# Memory.net
KiCad netlist of a schematic drawn in Altium Designer
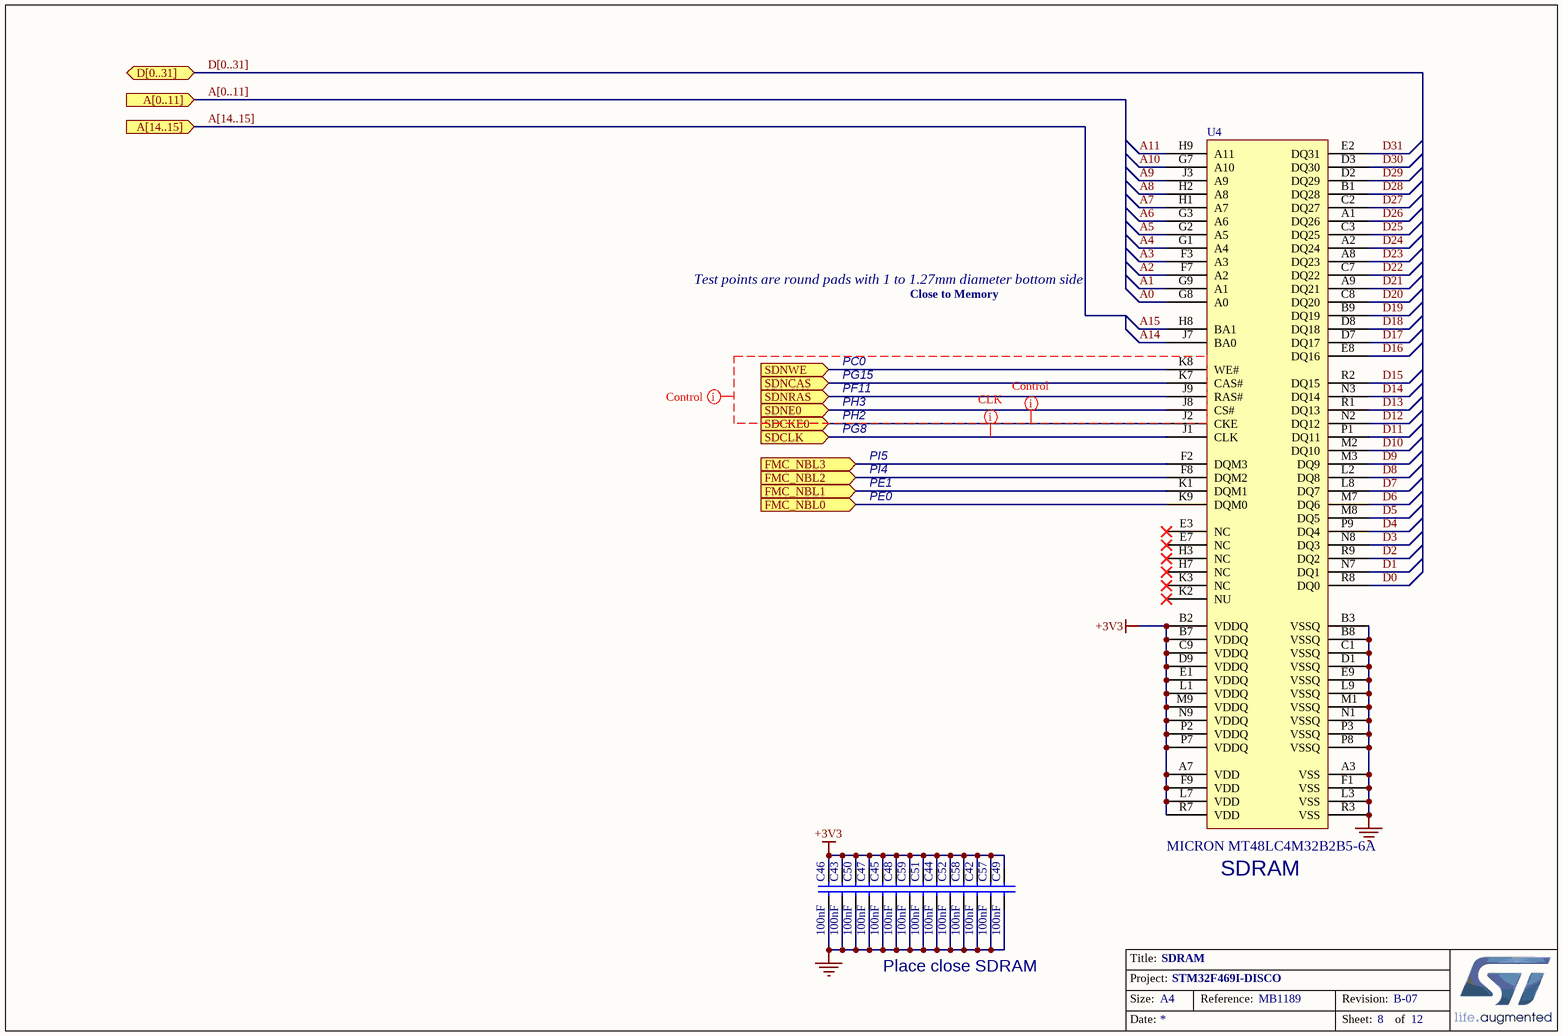
[diagram p0: Memory.SchDoc]

(export (version "E")
  (design (tool "Eeschema 10.0.6"))
  (components
    (comp (ref "C42")
      (value "100nF")
      (footprint "CAP - 0402")
      (description "Capacitor")
      (fields (field (name "PUBLISHER") "Altium Limited"))
      (libsource (lib "Miscellaneous Devices") (part "Cap"))
    )
    (comp (ref "C43")
      (value "100nF")
      (footprint "CAP - 0402")
      (description "Capacitor")
      (fields (field (name "PUBLISHER") "Altium Limited"))
      (libsource (lib "Miscellaneous Devices") (part "Cap"))
    )
    (comp (ref "C44")
      (value "100nF")
      (footprint "CAP - 0402")
      (description "Capacitor")
      (fields (field (name "PUBLISHER") "Altium Limited"))
      (libsource (lib "Miscellaneous Devices") (part "Cap"))
    )
    (comp (ref "C45")
      (value "100nF")
      (footprint "CAP - 0402")
      (description "Capacitor")
      (fields (field (name "PUBLISHER") "Altium Limited"))
      (libsource (lib "Miscellaneous Devices") (part "Cap"))
    )
    (comp (ref "C46")
      (value "100nF")
      (footprint "CAP - 0402")
      (description "Capacitor")
      (fields (field (name "PUBLISHER") "Altium Limited"))
      (libsource (lib "Miscellaneous Devices") (part "Cap"))
    )
    (comp (ref "C47")
      (value "100nF")
      (footprint "CAP - 0402")
      (description "Capacitor")
      (fields (field (name "PUBLISHER") "Altium Limited"))
      (libsource (lib "Miscellaneous Devices") (part "Cap"))
    )
    (comp (ref "C48")
      (value "100nF")
      (footprint "CAP - 0402")
      (description "Capacitor")
      (fields (field (name "PUBLISHER") "Altium Limited"))
      (libsource (lib "Miscellaneous Devices") (part "Cap"))
    )
    (comp (ref "C49")
      (value "100nF")
      (footprint "CAP - 0402")
      (description "Capacitor")
      (fields (field (name "PUBLISHER") "Altium Limited"))
      (libsource (lib "Miscellaneous Devices") (part "Cap"))
    )
    (comp (ref "C50")
      (value "100nF")
      (footprint "CAP - 0402")
      (description "Capacitor")
      (fields (field (name "PUBLISHER") "Altium Limited"))
      (libsource (lib "Miscellaneous Devices") (part "Cap"))
    )
    (comp (ref "C51")
      (value "100nF")
      (footprint "CAP - 0402")
      (description "Capacitor")
      (fields (field (name "PUBLISHER") "Altium Limited"))
      (libsource (lib "Miscellaneous Devices") (part "Cap"))
    )
    (comp (ref "C52")
      (value "100nF")
      (footprint "CAP - 0402")
      (description "Capacitor")
      (fields (field (name "PUBLISHER") "Altium Limited"))
      (libsource (lib "Miscellaneous Devices") (part "Cap"))
    )
    (comp (ref "C57")
      (value "100nF")
      (footprint "CAP - 0402")
      (description "Capacitor")
      (fields (field (name "PUBLISHER") "Altium Limited"))
      (libsource (lib "Miscellaneous Devices") (part "Cap"))
    )
    (comp (ref "C58")
      (value "100nF")
      (footprint "CAP - 0402")
      (description "Capacitor")
      (fields (field (name "PUBLISHER") "Altium Limited"))
      (libsource (lib "Miscellaneous Devices") (part "Cap"))
    )
    (comp (ref "C59")
      (value "100nF")
      (footprint "CAP - 0402")
      (description "Capacitor")
      (fields (field (name "PUBLISHER") "Altium Limited"))
      (libsource (lib "Miscellaneous Devices") (part "Cap"))
    )
    (comp (ref "U4")
      (value "MICRON MT48LC4M32B2B5-6A")
      (footprint "MICT-B5-90")
      (libsource (lib "mb1045") (part "MT48LC4M32B2B5"))
    )
  )
  (nets
    (net (code "1") (name "+3V3") (class "Default")
      (node (ref "C42") (pin "1") (pinfunction "1_1") (pintype "passive"))
      (node (ref "C43") (pin "1") (pinfunction "1_1") (pintype "passive"))
      (node (ref "C44") (pin "1") (pinfunction "1_1") (pintype "passive"))
      (node (ref "C45") (pin "1") (pinfunction "1_1") (pintype "passive"))
      (node (ref "C46") (pin "1") (pinfunction "1_1") (pintype "passive"))
      (node (ref "C47") (pin "1") (pinfunction "1_1") (pintype "passive"))
      (node (ref "C48") (pin "1") (pinfunction "1_1") (pintype "passive"))
      (node (ref "C49") (pin "1") (pinfunction "1_1") (pintype "passive"))
      (node (ref "C50") (pin "1") (pinfunction "1_1") (pintype "passive"))
      (node (ref "C51") (pin "1") (pinfunction "1_1") (pintype "passive"))
      (node (ref "C52") (pin "1") (pinfunction "1_1") (pintype "passive"))
      (node (ref "C57") (pin "1") (pinfunction "1_1") (pintype "passive"))
      (node (ref "C58") (pin "1") (pinfunction "1_1") (pintype "passive"))
      (node (ref "C59") (pin "1") (pinfunction "1_1") (pintype "passive"))
      (node (ref "U4") (pin "A7") (pinfunction "VDD_A7") (pintype "passive"))
      (node (ref "U4") (pin "B2") (pinfunction "VDDQ_B2") (pintype "passive"))
      (node (ref "U4") (pin "B7") (pinfunction "VDDQ_B7") (pintype "passive"))
      (node (ref "U4") (pin "C9") (pinfunction "VDDQ_C9") (pintype "passive"))
      (node (ref "U4") (pin "D9") (pinfunction "VDDQ_D9") (pintype "passive"))
      (node (ref "U4") (pin "E1") (pinfunction "VDDQ_E1") (pintype "passive"))
      (node (ref "U4") (pin "F9") (pinfunction "VDD_F9") (pintype "passive"))
      (node (ref "U4") (pin "L1") (pinfunction "VDDQ_L1") (pintype "passive"))
      (node (ref "U4") (pin "L7") (pinfunction "VDD_L7") (pintype "passive"))
      (node (ref "U4") (pin "M9") (pinfunction "VDDQ_M9") (pintype "passive"))
      (node (ref "U4") (pin "N9") (pinfunction "VDDQ_N9") (pintype "passive"))
      (node (ref "U4") (pin "P2") (pinfunction "VDDQ_P2") (pintype "passive"))
      (node (ref "U4") (pin "P7") (pinfunction "VDDQ_P7") (pintype "passive"))
      (node (ref "U4") (pin "R7") (pinfunction "VDD_R7") (pintype "passive"))
    )
    (net (code "2") (name "/A0") (class "Default")
      (node (ref "U4") (pin "G8") (pinfunction "A0_G8") (pintype "passive"))
    )
    (net (code "3") (name "/A1") (class "Default")
      (node (ref "U4") (pin "G9") (pinfunction "A1_G9") (pintype "passive"))
    )
    (net (code "4") (name "/A2") (class "Default")
      (node (ref "U4") (pin "F7") (pinfunction "A2_F7") (pintype "passive"))
    )
    (net (code "5") (name "/A3") (class "Default")
      (node (ref "U4") (pin "F3") (pinfunction "A3_F3") (pintype "passive"))
    )
    (net (code "6") (name "/A4") (class "Default")
      (node (ref "U4") (pin "G1") (pinfunction "A4_G1") (pintype "passive"))
    )
    (net (code "7") (name "/A5") (class "Default")
      (node (ref "U4") (pin "G2") (pinfunction "A5_G2") (pintype "passive"))
    )
    (net (code "8") (name "/A6") (class "Default")
      (node (ref "U4") (pin "G3") (pinfunction "A6_G3") (pintype "passive"))
    )
    (net (code "9") (name "/A7") (class "Default")
      (node (ref "U4") (pin "H1") (pinfunction "A7_H1") (pintype "passive"))
    )
    (net (code "10") (name "/A8") (class "Default")
      (node (ref "U4") (pin "H2") (pinfunction "A8_H2") (pintype "passive"))
    )
    (net (code "11") (name "/A9") (class "Default")
      (node (ref "U4") (pin "J3") (pinfunction "A9_J3") (pintype "passive"))
    )
    (net (code "12") (name "/A10") (class "Default")
      (node (ref "U4") (pin "G7") (pinfunction "A10_G7") (pintype "passive"))
    )
    (net (code "13") (name "/A11") (class "Default")
      (node (ref "U4") (pin "H9") (pinfunction "A11_H9") (pintype "passive"))
    )
    (net (code "14") (name "/A14") (class "Default")
      (node (ref "U4") (pin "J7") (pinfunction "BA0_J7") (pintype "passive"))
    )
    (net (code "15") (name "/A15") (class "Default")
      (node (ref "U4") (pin "H8") (pinfunction "BA1_H8") (pintype "passive"))
    )
    (net (code "18") (name "/D0") (class "Default")
      (node (ref "U4") (pin "R8") (pinfunction "DQ0_R8") (pintype "passive"))
    )
    (net (code "19") (name "/D1") (class "Default")
      (node (ref "U4") (pin "N7") (pinfunction "DQ1_N7") (pintype "passive"))
    )
    (net (code "20") (name "/D2") (class "Default")
      (node (ref "U4") (pin "R9") (pinfunction "DQ2_R9") (pintype "passive"))
    )
    (net (code "21") (name "/D3") (class "Default")
      (node (ref "U4") (pin "N8") (pinfunction "DQ3_N8") (pintype "passive"))
    )
    (net (code "22") (name "/D4") (class "Default")
      (node (ref "U4") (pin "P9") (pinfunction "DQ4_P9") (pintype "passive"))
    )
    (net (code "23") (name "/D5") (class "Default")
      (node (ref "U4") (pin "M8") (pinfunction "DQ5_M8") (pintype "passive"))
    )
    (net (code "24") (name "/D6") (class "Default")
      (node (ref "U4") (pin "M7") (pinfunction "DQ6_M7") (pintype "passive"))
    )
    (net (code "25") (name "/D7") (class "Default")
      (node (ref "U4") (pin "L8") (pinfunction "DQ7_L8") (pintype "passive"))
    )
    (net (code "26") (name "/D8") (class "Default")
      (node (ref "U4") (pin "L2") (pinfunction "DQ8_L2") (pintype "passive"))
    )
    (net (code "27") (name "/D9") (class "Default")
      (node (ref "U4") (pin "M3") (pinfunction "DQ9_M3") (pintype "passive"))
    )
    (net (code "28") (name "/D10") (class "Default")
      (node (ref "U4") (pin "M2") (pinfunction "DQ10_M2") (pintype "passive"))
    )
    (net (code "29") (name "/D11") (class "Default")
      (node (ref "U4") (pin "P1") (pinfunction "DQ11_P1") (pintype "passive"))
    )
    (net (code "30") (name "/D12") (class "Default")
      (node (ref "U4") (pin "N2") (pinfunction "DQ12_N2") (pintype "passive"))
    )
    (net (code "31") (name "/D13") (class "Default")
      (node (ref "U4") (pin "R1") (pinfunction "DQ13_R1") (pintype "passive"))
    )
    (net (code "32") (name "/D14") (class "Default")
      (node (ref "U4") (pin "N3") (pinfunction "DQ14_N3") (pintype "passive"))
    )
    (net (code "33") (name "/D15") (class "Default")
      (node (ref "U4") (pin "R2") (pinfunction "DQ15_R2") (pintype "passive"))
    )
    (net (code "34") (name "/D16") (class "Default")
      (node (ref "U4") (pin "E8") (pinfunction "DQ16_E8") (pintype "passive"))
    )
    (net (code "35") (name "/D17") (class "Default")
      (node (ref "U4") (pin "D7") (pinfunction "DQ17_D7") (pintype "passive"))
    )
    (net (code "36") (name "/D18") (class "Default")
      (node (ref "U4") (pin "D8") (pinfunction "DQ18_D8") (pintype "passive"))
    )
    (net (code "37") (name "/D19") (class "Default")
      (node (ref "U4") (pin "B9") (pinfunction "DQ19_B9") (pintype "passive"))
    )
    (net (code "38") (name "/D20") (class "Default")
      (node (ref "U4") (pin "C8") (pinfunction "DQ20_C8") (pintype "passive"))
    )
    (net (code "39") (name "/D21") (class "Default")
      (node (ref "U4") (pin "A9") (pinfunction "DQ21_A9") (pintype "passive"))
    )
    (net (code "40") (name "/D22") (class "Default")
      (node (ref "U4") (pin "C7") (pinfunction "DQ22_C7") (pintype "passive"))
    )
    (net (code "41") (name "/D23") (class "Default")
      (node (ref "U4") (pin "A8") (pinfunction "DQ23_A8") (pintype "passive"))
    )
    (net (code "42") (name "/D24") (class "Default")
      (node (ref "U4") (pin "A2") (pinfunction "DQ24_A2") (pintype "passive"))
    )
    (net (code "43") (name "/D25") (class "Default")
      (node (ref "U4") (pin "C3") (pinfunction "DQ25_C3") (pintype "passive"))
    )
    (net (code "44") (name "/D26") (class "Default")
      (node (ref "U4") (pin "A1") (pinfunction "DQ26_A1") (pintype "passive"))
    )
    (net (code "45") (name "/D27") (class "Default")
      (node (ref "U4") (pin "C2") (pinfunction "DQ27_C2") (pintype "passive"))
    )
    (net (code "46") (name "/D28") (class "Default")
      (node (ref "U4") (pin "B1") (pinfunction "DQ28_B1") (pintype "passive"))
    )
    (net (code "47") (name "/D29") (class "Default")
      (node (ref "U4") (pin "D2") (pinfunction "DQ29_D2") (pintype "passive"))
    )
    (net (code "48") (name "/D30") (class "Default")
      (node (ref "U4") (pin "D3") (pinfunction "DQ30_D3") (pintype "passive"))
    )
    (net (code "49") (name "/D31") (class "Default")
      (node (ref "U4") (pin "E2") (pinfunction "DQ31_E2") (pintype "passive"))
    )
    (net (code "51") (name "/FMC_NBL0") (class "Default")
      (node (ref "U4") (pin "K9") (pinfunction "DQM0_K9") (pintype "passive"))
    )
    (net (code "52") (name "/FMC_NBL1") (class "Default")
      (node (ref "U4") (pin "K1") (pinfunction "DQM1_K1") (pintype "passive"))
    )
    (net (code "53") (name "/FMC_NBL2") (class "Default")
      (node (ref "U4") (pin "F8") (pinfunction "DQM2_F8") (pintype "passive"))
    )
    (net (code "54") (name "/FMC_NBL3") (class "Default")
      (node (ref "U4") (pin "F2") (pinfunction "DQM3_F2") (pintype "passive"))
    )
    (net (code "55") (name "/SDCKE0") (class "Default")
      (node (ref "U4") (pin "J2") (pinfunction "CKE_J2") (pintype "passive"))
    )
    (net (code "56") (name "/SDCLK") (class "Default")
      (node (ref "U4") (pin "J1") (pinfunction "CLK_J1") (pintype "passive"))
    )
    (net (code "57") (name "/SDNCAS") (class "Default")
      (node (ref "U4") (pin "K7") (pinfunction "CAS#_K7") (pintype "passive"))
    )
    (net (code "58") (name "/SDNE0") (class "Default")
      (node (ref "U4") (pin "J8") (pinfunction "CS#_J8") (pintype "passive"))
    )
    (net (code "59") (name "/SDNRAS") (class "Default")
      (node (ref "U4") (pin "J9") (pinfunction "RAS#_J9") (pintype "passive"))
    )
    (net (code "60") (name "/SDNWE") (class "Default")
      (node (ref "U4") (pin "K8") (pinfunction "WE#_K8") (pintype "passive"))
    )
    (net (code "61") (name "GND") (class "Default")
      (node (ref "C42") (pin "2") (pinfunction "2_2") (pintype "passive"))
      (node (ref "C43") (pin "2") (pinfunction "2_2") (pintype "passive"))
      (node (ref "C44") (pin "2") (pinfunction "2_2") (pintype "passive"))
      (node (ref "C45") (pin "2") (pinfunction "2_2") (pintype "passive"))
      (node (ref "C46") (pin "2") (pinfunction "2_2") (pintype "passive"))
      (node (ref "C47") (pin "2") (pinfunction "2_2") (pintype "passive"))
      (node (ref "C48") (pin "2") (pinfunction "2_2") (pintype "passive"))
      (node (ref "C49") (pin "2") (pinfunction "2_2") (pintype "passive"))
      (node (ref "C50") (pin "2") (pinfunction "2_2") (pintype "passive"))
      (node (ref "C51") (pin "2") (pinfunction "2_2") (pintype "passive"))
      (node (ref "C52") (pin "2") (pinfunction "2_2") (pintype "passive"))
      (node (ref "C57") (pin "2") (pinfunction "2_2") (pintype "passive"))
      (node (ref "C58") (pin "2") (pinfunction "2_2") (pintype "passive"))
      (node (ref "C59") (pin "2") (pinfunction "2_2") (pintype "passive"))
      (node (ref "U4") (pin "A3") (pinfunction "VSS_A3") (pintype "passive"))
      (node (ref "U4") (pin "B3") (pinfunction "VSSQ_B3") (pintype "passive"))
      (node (ref "U4") (pin "B8") (pinfunction "VSSQ_B8") (pintype "passive"))
      (node (ref "U4") (pin "C1") (pinfunction "VSSQ_C1") (pintype "passive"))
      (node (ref "U4") (pin "D1") (pinfunction "VSSQ_D1") (pintype "passive"))
      (node (ref "U4") (pin "E9") (pinfunction "VSSQ_E9") (pintype "passive"))
      (node (ref "U4") (pin "F1") (pinfunction "VSS_F1") (pintype "passive"))
      (node (ref "U4") (pin "L3") (pinfunction "VSS_L3") (pintype "passive"))
      (node (ref "U4") (pin "L9") (pinfunction "VSSQ_L9") (pintype "passive"))
      (node (ref "U4") (pin "M1") (pinfunction "VSSQ_M1") (pintype "passive"))
      (node (ref "U4") (pin "N1") (pinfunction "VSSQ_N1") (pintype "passive"))
      (node (ref "U4") (pin "P3") (pinfunction "VSSQ_P3") (pintype "passive"))
      (node (ref "U4") (pin "P8") (pinfunction "VSSQ_P8") (pintype "passive"))
      (node (ref "U4") (pin "R3") (pinfunction "VSS_R3") (pintype "passive"))
    )
    (net (code "62") (name "unconnected-(U4-NC-PadE3)") (class "Default")
      (node (ref "U4") (pin "E3") (pinfunction "NC_E3") (pintype "passive+no_connect"))
    )
    (net (code "63") (name "unconnected-(U4-NC-PadE7)") (class "Default")
      (node (ref "U4") (pin "E7") (pinfunction "NC_E7") (pintype "passive+no_connect"))
    )
    (net (code "64") (name "unconnected-(U4-NC-PadH3)") (class "Default")
      (node (ref "U4") (pin "H3") (pinfunction "NC_H3") (pintype "passive+no_connect"))
    )
    (net (code "65") (name "unconnected-(U4-NC-PadH7)") (class "Default")
      (node (ref "U4") (pin "H7") (pinfunction "NC_H7") (pintype "passive+no_connect"))
    )
    (net (code "66") (name "unconnected-(U4-NC-PadK3)") (class "Default")
      (node (ref "U4") (pin "K3") (pinfunction "NC_K3") (pintype "passive+no_connect"))
    )
    (net (code "67") (name "unconnected-(U4-NU-PadK2)") (class "Default")
      (node (ref "U4") (pin "K2") (pinfunction "NU_K2") (pintype "passive+no_connect"))
    )
  )
)
